# Team13TH.net
KiCad netlist of a schematic drawn in Altium Designer
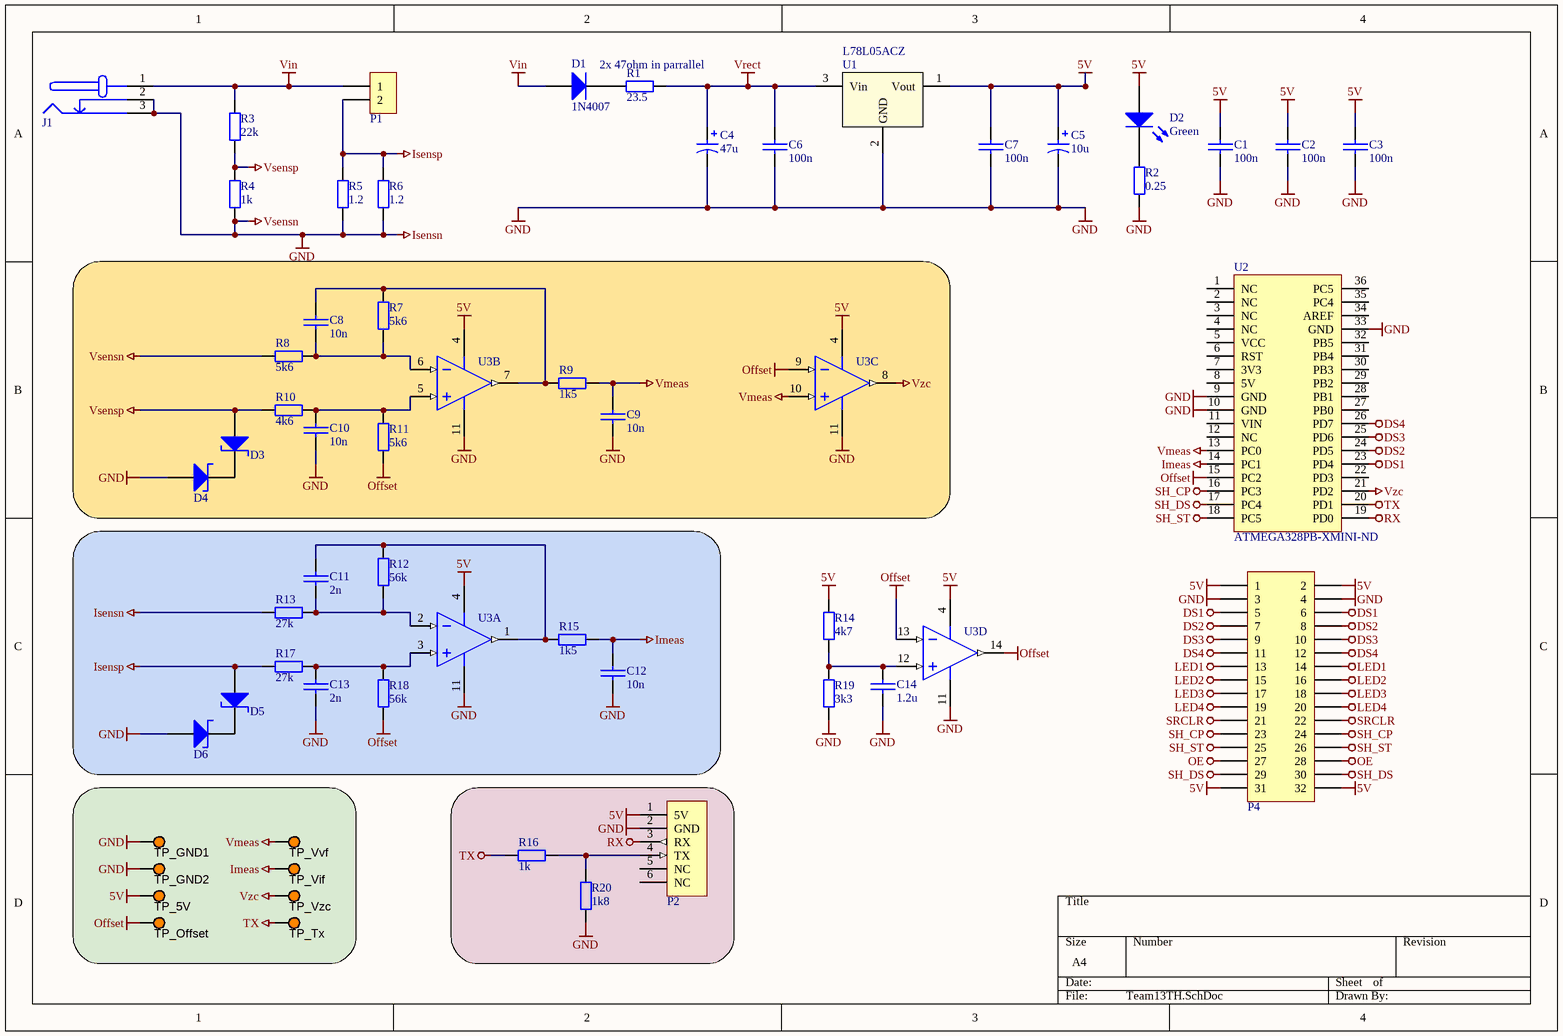
[diagram p0: Team13TH.SchDoc]

(export (version "E")
  (design (tool "Eeschema 10.0.6"))
  (components
    (comp (ref "C1")
      (value "100n")
      (footprint "CCAP-5P0")
      (description "TH ceramic capacitor with 5mm pitch")
      (libsource (lib "EE209_Library") (part "CerCap_TH_5P0"))
    )
    (comp (ref "C2")
      (value "100n")
      (footprint "CCAP-5P0")
      (description "TH ceramic capacitor with 5mm pitch")
      (libsource (lib "EE209_Library") (part "CerCap_TH_5P0"))
    )
    (comp (ref "C3")
      (value "100n")
      (footprint "CCAP-5P0")
      (description "TH ceramic capacitor with 5mm pitch")
      (libsource (lib "EE209_Library") (part "CerCap_TH_5P0"))
    )
    (comp (ref "C4")
      (value "47u")
      (footprint "CAP-RAD-2.5mm Pitch")
      (description "Electrolytic capacitor with radial package, 2mm pitch and 5.2mm diameter")
      (fields (field (name "PUBLISHER") "Altium Limited"))
      (libsource (lib "EE209_Library") (part "ElecCap_TH_2P0"))
    )
    (comp (ref "C5")
      (value "10u")
      (footprint "CAP-RAD-2.5mm Pitch")
      (description "Electrolytic capacitor with radial package, 2mm pitch and 5.2mm diameter")
      (fields (field (name "PUBLISHER") "Altium Limited"))
      (libsource (lib "EE209_Library") (part "ElecCap_TH_2P0"))
    )
    (comp (ref "C6")
      (value "100n")
      (footprint "CCAP-5P0")
      (description "TH ceramic capacitor with 5mm pitch")
      (libsource (lib "EE209_Library") (part "CerCap_TH_5P0"))
    )
    (comp (ref "C7")
      (value "100n")
      (footprint "CCAP-5P0")
      (description "TH ceramic capacitor with 5mm pitch")
      (libsource (lib "EE209_Library") (part "CerCap_TH_5P0"))
    )
    (comp (ref "C8")
      (value "10n")
      (footprint "CCAP-5P0")
      (description "TH ceramic capacitor with 5mm pitch")
      (libsource (lib "EE209_Library") (part "CerCap_TH_5P0"))
    )
    (comp (ref "C9")
      (value "10n")
      (footprint "CCAP-5P0")
      (description "TH ceramic capacitor with 5mm pitch")
      (libsource (lib "EE209_Library") (part "CerCap_TH_5P0"))
    )
    (comp (ref "C10")
      (value "10n")
      (footprint "CCAP-5P0")
      (description "TH ceramic capacitor with 5mm pitch")
      (libsource (lib "EE209_Library") (part "CerCap_TH_5P0"))
    )
    (comp (ref "C11")
      (value "2n")
      (footprint "CCAP-5P0")
      (description "TH ceramic capacitor with 5mm pitch")
      (libsource (lib "EE209_Library") (part "CerCap_TH_5P0"))
    )
    (comp (ref "C12")
      (value "10n")
      (footprint "CCAP-5P0")
      (description "TH ceramic capacitor with 5mm pitch")
      (libsource (lib "EE209_Library") (part "CerCap_TH_5P0"))
    )
    (comp (ref "C13")
      (value "2n")
      (footprint "CCAP-5P0")
      (description "TH ceramic capacitor with 5mm pitch")
      (libsource (lib "EE209_Library") (part "CerCap_TH_5P0"))
    )
    (comp (ref "C14")
      (value "1.2u")
      (footprint "CCAP-5P0")
      (description "TH ceramic capacitor with 5mm pitch")
      (libsource (lib "EE209_Library") (part "CerCap_TH_5P0"))
    )
    (comp (ref "D1")
      (value "1N4007")
      (footprint "1N4007-MFG")
      (description "1N4007 1000V standard axial diode")
      (libsource (lib "EE209_Library") (part "1N4007_TH_4AX0"))
    )
    (comp (ref "D2")
      (value "Green")
      (footprint "LED")
      (description "Typical throughole GaAs LED with 2.54mm pitch")
      (fields (field (name "MANUFACTURER") "Generic Components") (field (name "PUBLISHER") "Altium Limited"))
      (libsource (lib "EE209_Library") (part "LED_TH_2P54"))
    )
    (comp (ref "D3")
      (value "BZX79-CXVX")
      (footprint "AXIAL-Zener-0.4")
      (description "Axial zener diode BZX79 series")
      (fields
        (field (name "MANUFACTURER") "Nexperia USA Inc.")
        (field (name "MANUFACTURER PART NUMBER") "BZX79-C4V7,143")
      )
      (libsource (lib "EE209_Library") (part "Zener_TH_4AX0"))
    )
    (comp (ref "D4")
      (value "BZX79-CXVX")
      (footprint "AXIAL-Zener-0.4")
      (description "Axial zener diode BZX79 series")
      (fields
        (field (name "MANUFACTURER") "Nexperia USA Inc.")
        (field (name "MANUFACTURER PART NUMBER") "BZX79-C4V7,143")
      )
      (libsource (lib "EE209_Library") (part "Zener_TH_4AX0"))
    )
    (comp (ref "D5")
      (value "BZX79-CXVX")
      (footprint "AXIAL-Zener-0.4")
      (description "Axial zener diode BZX79 series")
      (fields
        (field (name "MANUFACTURER") "Nexperia USA Inc.")
        (field (name "MANUFACTURER PART NUMBER") "BZX79-C4V7,143")
      )
      (libsource (lib "EE209_Library") (part "Zener_TH_4AX0"))
    )
    (comp (ref "D6")
      (value "BZX79-CXVX")
      (footprint "AXIAL-Zener-0.4")
      (description "Axial zener diode BZX79 series")
      (fields
        (field (name "MANUFACTURER") "Nexperia USA Inc.")
        (field (name "MANUFACTURER PART NUMBER") "BZX79-C4V7,143")
      )
      (libsource (lib "EE209_Library") (part "Zener_TH_4AX0"))
    )
    (comp (ref "J1")
      (value "DC barrel jack")
      (footprint "AC-Socket")
      (description "DC barrel jack connection to AC source")
      (libsource (lib "EE209_Library") (part "AC_Input"))
    )
    (comp (ref "P1")
      (value "Dual Banana Plugs")
      (footprint "Dual Banana Plug")
      (description "Dual banana plugs connection to the AC load")
      (fields (field (name "PUBLISHER") "Altium Limited"))
      (libsource (lib "EE209_Library") (part "AC_Output"))
    )
    (comp (ref "P2")
      (value "BLE Module Header")
      (footprint "HM10_HDR1X6")
      (description "2.54mm pitch 6-pin header for BLE module")
      (fields (field (name "PUBLISHER") "Altium Limited"))
      (libsource (lib "EE209_Library") (part "BLEModule_TH"))
    )
    (comp (ref "P4")
      (value "Display")
      (footprint "Display")
      (description "16-Pin Header Connecting Display")
      (libsource (lib "EE209_Library") (part "Display"))
    )
    (comp (ref "R1")
      (value "23.5")
      (footprint "AXIAL-0.4")
      (description "Through hole resistor")
      (fields (field (name "PUBLISHER") "Altium Limited"))
      (libsource (lib "") (part "Res_TH_0AX4_1"))
    )
    (comp (ref "R2")
      (value "0.25")
      (footprint "AXIAL-0.4")
      (description "Through hole resistor")
      (fields (field (name "PUBLISHER") "Altium Limited"))
      (libsource (lib "EE209_Library") (part "Res_TH_0AX4"))
    )
    (comp (ref "R3")
      (value "22k")
      (footprint "AXIAL-0.4")
      (description "Through hole resistor")
      (fields (field (name "PUBLISHER") "Altium Limited"))
      (libsource (lib "EE209_Library") (part "Res_TH_0AX4"))
    )
    (comp (ref "R4")
      (value "1k")
      (footprint "AXIAL-0.4")
      (description "Through hole resistor")
      (fields (field (name "PUBLISHER") "Altium Limited"))
      (libsource (lib "EE209_Library") (part "Res_TH_0AX4"))
    )
    (comp (ref "R5")
      (value "1.2")
      (footprint "AXIAL-0.4")
      (description "Through hole resistor")
      (fields (field (name "PUBLISHER") "Altium Limited"))
      (libsource (lib "EE209_Library") (part "Res_TH_0AX4"))
    )
    (comp (ref "R6")
      (value "1.2")
      (footprint "AXIAL-0.4")
      (description "Through hole resistor")
      (fields (field (name "PUBLISHER") "Altium Limited"))
      (libsource (lib "EE209_Library") (part "Res_TH_0AX4"))
    )
    (comp (ref "R7")
      (value "5k6")
      (footprint "AXIAL-0.4")
      (description "Through hole resistor")
      (fields (field (name "PUBLISHER") "Altium Limited"))
      (libsource (lib "EE209_Library") (part "Res_TH_0AX4"))
    )
    (comp (ref "R8")
      (value "5k6")
      (footprint "AXIAL-0.4")
      (description "Through hole resistor")
      (fields (field (name "PUBLISHER") "Altium Limited"))
      (libsource (lib "") (part "Res_TH_0AX4_1"))
    )
    (comp (ref "R9")
      (value "1k5")
      (footprint "AXIAL-0.4")
      (description "Through hole resistor")
      (fields (field (name "PUBLISHER") "Altium Limited"))
      (libsource (lib "") (part "Res_TH_0AX4_1"))
    )
    (comp (ref "R10")
      (value "4k6")
      (footprint "AXIAL-0.4")
      (description "Through hole resistor")
      (fields (field (name "PUBLISHER") "Altium Limited"))
      (libsource (lib "") (part "Res_TH_0AX4_2"))
    )
    (comp (ref "R11")
      (value "5k6")
      (footprint "AXIAL-0.4")
      (description "Through hole resistor")
      (fields (field (name "PUBLISHER") "Altium Limited"))
      (libsource (lib "EE209_Library") (part "Res_TH_0AX4"))
    )
    (comp (ref "R12")
      (value "56k")
      (footprint "AXIAL-0.4")
      (description "Through hole resistor")
      (fields (field (name "PUBLISHER") "Altium Limited"))
      (libsource (lib "EE209_Library") (part "Res_TH_0AX4"))
    )
    (comp (ref "R13")
      (value "27k")
      (footprint "AXIAL-0.4")
      (description "Through hole resistor")
      (fields (field (name "PUBLISHER") "Altium Limited"))
      (libsource (lib "") (part "Res_TH_0AX4_1"))
    )
    (comp (ref "R14")
      (value "4k7")
      (footprint "AXIAL-0.4")
      (description "Through hole resistor")
      (fields (field (name "PUBLISHER") "Altium Limited"))
      (libsource (lib "EE209_Library") (part "Res_TH_0AX4"))
    )
    (comp (ref "R15")
      (value "1k5")
      (footprint "AXIAL-0.4")
      (description "Through hole resistor")
      (fields (field (name "PUBLISHER") "Altium Limited"))
      (libsource (lib "") (part "Res_TH_0AX4_1"))
    )
    (comp (ref "R16")
      (value "1k")
      (footprint "AXIAL-0.4")
      (description "Through hole resistor")
      (fields (field (name "PUBLISHER") "Altium Limited"))
      (libsource (lib "") (part "Res_TH_0AX4_1"))
    )
    (comp (ref "R17")
      (value "27k")
      (footprint "AXIAL-0.4")
      (description "Through hole resistor")
      (fields (field (name "PUBLISHER") "Altium Limited"))
      (libsource (lib "") (part "Res_TH_0AX4_2"))
    )
    (comp (ref "R18")
      (value "56k")
      (footprint "AXIAL-0.4")
      (description "Through hole resistor")
      (fields (field (name "PUBLISHER") "Altium Limited"))
      (libsource (lib "EE209_Library") (part "Res_TH_0AX4"))
    )
    (comp (ref "R19")
      (value "3k3")
      (footprint "AXIAL-0.4")
      (description "Through hole resistor")
      (fields (field (name "PUBLISHER") "Altium Limited"))
      (libsource (lib "EE209_Library") (part "Res_TH_0AX4"))
    )
    (comp (ref "R20")
      (value "1k8")
      (footprint "AXIAL-0.4")
      (description "Through hole resistor")
      (fields (field (name "PUBLISHER") "Altium Limited"))
      (libsource (lib "EE209_Library") (part "Res_TH_0AX4"))
    )
    (comp (ref "TP_5V")
      (value "5003")
      (footprint "TP_TH")
      (description "Test Point, Orange, 1-Pin THD, RoHS")
      (libsource (lib "EE209_Library") (part "TestPoint"))
    )
    (comp (ref "TP_GND1")
      (value "5003")
      (footprint "TP_TH")
      (description "Test Point, Orange, 1-Pin THD, RoHS")
      (libsource (lib "EE209_Library") (part "TestPoint"))
    )
    (comp (ref "TP_GND2")
      (value "5003")
      (footprint "TP_TH")
      (description "Test Point, Orange, 1-Pin THD, RoHS")
      (libsource (lib "EE209_Library") (part "TestPoint"))
    )
    (comp (ref "TP_Offset")
      (value "5003")
      (footprint "TP_TH")
      (description "Test Point, Orange, 1-Pin THD, RoHS")
      (libsource (lib "EE209_Library") (part "TestPoint"))
    )
    (comp (ref "TP_Tx")
      (value "5003")
      (footprint "TP_TH")
      (description "Test Point, Orange, 1-Pin THD, RoHS")
      (libsource (lib "EE209_Library") (part "TestPoint"))
    )
    (comp (ref "TP_Vif")
      (value "5003")
      (footprint "TP_TH")
      (description "Test Point, Orange, 1-Pin THD, RoHS")
      (libsource (lib "EE209_Library") (part "TestPoint"))
    )
    (comp (ref "TP_Vvf")
      (value "5003")
      (footprint "TP_TH")
      (description "Test Point, Orange, 1-Pin THD, RoHS")
      (libsource (lib "EE209_Library") (part "TestPoint"))
    )
    (comp (ref "TP_Vzc")
      (value "5003")
      (footprint "TP_TH")
      (description "Test Point, Orange, 1-Pin THD, RoHS")
      (libsource (lib "EE209_Library") (part "TestPoint"))
    )
    (comp (ref "U1")
      (value "L78L05ACZ")
      (footprint "TO-92")
      (description "Voltage Regulator 5V")
      (fields
        (field (name "MANUFACTURER") "ON Semiconductor")
        (field (name "MANUFACTURER PART NUMBER") "LM78L05ACZX")
      )
      (libsource (lib "EE209_Library") (part "L78L05_TH_TO92"))
    )
    (comp (ref "U2")
      (value "ATmega328PB Xplained Mini Header")
      (footprint "ATmeg328P Xplained")
      (description "Dual 18-pin headers connecting to ATmega328PB Xplained Mini")
      (fields
        (field (name "MANUFACTURER") "Microchip Technology")
        (field (name "MANUFACTURER PART NUMBER") "ATMEGA328PB-XMINI")
        (field (name "SUPPLIER PART NUMBER 1") "ATMEGA328PB-XMINI-ND")
      )
      (libsource (lib "EE209_Library") (part "ATmega328PBXplained_TH"))
    )
    (comp (ref "U3")
      (value "LM324")
      (footprint "DIP-14")
      (description "IC OPAMP GP 14DIP")
      (fields
        (field (name "MANUFACTURER") "ON Semiconductor")
        (field (name "MANUFACTURER PART NUMBER") "LM324N")
      )
      (libsource (lib "EE209_Library") (part "LM324N_TH_DIP16"))
    )
  )
  (nets
    (net (code "1") (name "5V") (class "Default")
      (node (ref "C1") (pin "1") (pinfunction "1_1") (pintype "passive"))
      (node (ref "C2") (pin "1") (pinfunction "1_1") (pintype "passive"))
      (node (ref "C3") (pin "1") (pinfunction "1_1") (pintype "passive"))
      (node (ref "C5") (pin "1") (pinfunction "1_1") (pintype "passive"))
      (node (ref "C7") (pin "1") (pinfunction "1_1") (pintype "passive"))
      (node (ref "D2") (pin "1") (pinfunction "A_1") (pintype "passive"))
      (node (ref "P2") (pin "1") (pinfunction "5V_1") (pintype "passive"))
      (node (ref "P4") (pin "1") (pinfunction "1_1") (pintype "passive"))
      (node (ref "P4") (pin "2") (pinfunction "2_2") (pintype "passive"))
      (node (ref "P4") (pin "31") (pinfunction "31_31") (pintype "passive"))
      (node (ref "P4") (pin "32") (pinfunction "32_32") (pintype "passive"))
      (node (ref "R14") (pin "2") (pinfunction "2_2") (pintype "passive"))
      (node (ref "TP_5V") (pin "1") (pinfunction "1_1") (pintype "passive"))
      (node (ref "U1") (pin "1") (pinfunction "Vout_1") (pintype "passive"))
      (node (ref "U3") (pin "4") (pinfunction "VDD_4") (pintype "power_in"))
    )
    (net (code "2") (name "DS1") (class "Default")
      (node (ref "P4") (pin "5") (pinfunction "5_5") (pintype "passive"))
      (node (ref "P4") (pin "6") (pinfunction "6_6") (pintype "passive"))
      (node (ref "U2") (pin "23") (pinfunction "PD4_23") (pintype "passive"))
    )
    (net (code "3") (name "DS2") (class "Default")
      (node (ref "P4") (pin "7") (pinfunction "7_7") (pintype "passive"))
      (node (ref "P4") (pin "8") (pinfunction "8_8") (pintype "passive"))
      (node (ref "U2") (pin "24") (pinfunction "PD5_24") (pintype "passive"))
    )
    (net (code "4") (name "DS3") (class "Default")
      (node (ref "P4") (pin "10") (pinfunction "10_10") (pintype "passive"))
      (node (ref "P4") (pin "9") (pinfunction "9_9") (pintype "passive"))
      (node (ref "U2") (pin "25") (pinfunction "PD6_25") (pintype "passive"))
    )
    (net (code "5") (name "DS4") (class "Default")
      (node (ref "P4") (pin "11") (pinfunction "11_11") (pintype "passive"))
      (node (ref "P4") (pin "12") (pinfunction "12_12") (pintype "passive"))
      (node (ref "U2") (pin "26") (pinfunction "PD7_26") (pintype "passive"))
    )
    (net (code "6") (name "GND") (class "Default")
      (node (ref "C1") (pin "2") (pinfunction "2_2") (pintype "passive"))
      (node (ref "C10") (pin "2") (pinfunction "2_2") (pintype "passive"))
      (node (ref "C12") (pin "2") (pinfunction "2_2") (pintype "passive"))
      (node (ref "C13") (pin "2") (pinfunction "2_2") (pintype "passive"))
      (node (ref "C14") (pin "2") (pinfunction "2_2") (pintype "passive"))
      (node (ref "C2") (pin "2") (pinfunction "2_2") (pintype "passive"))
      (node (ref "C3") (pin "2") (pinfunction "2_2") (pintype "passive"))
      (node (ref "C4") (pin "2") (pinfunction "2_2") (pintype "passive"))
      (node (ref "C5") (pin "2") (pinfunction "2_2") (pintype "passive"))
      (node (ref "C6") (pin "2") (pinfunction "2_2") (pintype "passive"))
      (node (ref "C7") (pin "2") (pinfunction "2_2") (pintype "passive"))
      (node (ref "C9") (pin "2") (pinfunction "2_2") (pintype "passive"))
      (node (ref "D4") (pin "1") (pinfunction "A_1") (pintype "passive"))
      (node (ref "D6") (pin "1") (pinfunction "A_1") (pintype "passive"))
      (node (ref "J1") (pin "2") (pinfunction "GND_ALT_2") (pintype "power_in"))
      (node (ref "J1") (pin "3") (pinfunction "GND_3") (pintype "power_in"))
      (node (ref "P2") (pin "2") (pinfunction "GND_2") (pintype "passive"))
      (node (ref "P4") (pin "3") (pinfunction "3_3") (pintype "passive"))
      (node (ref "P4") (pin "4") (pinfunction "4_4") (pintype "passive"))
      (node (ref "R13") (pin "1") (pinfunction "1_1") (pintype "passive"))
      (node (ref "R19") (pin "1") (pinfunction "1_1") (pintype "passive"))
      (node (ref "R2") (pin "1") (pinfunction "1_1") (pintype "passive"))
      (node (ref "R20") (pin "1") (pinfunction "1_1") (pintype "passive"))
      (node (ref "R4") (pin "1") (pinfunction "1_1") (pintype "passive"))
      (node (ref "R5") (pin "1") (pinfunction "1_1") (pintype "passive"))
      (node (ref "R6") (pin "1") (pinfunction "1_1") (pintype "passive"))
      (node (ref "R8") (pin "1") (pinfunction "1_1") (pintype "passive"))
      (node (ref "TP_GND1") (pin "1") (pinfunction "1_1") (pintype "passive"))
      (node (ref "TP_GND2") (pin "1") (pinfunction "1_1") (pintype "passive"))
      (node (ref "U1") (pin "2") (pinfunction "GND_2") (pintype "passive"))
      (node (ref "U2") (pin "10") (pinfunction "GND_10") (pintype "power_in"))
      (node (ref "U2") (pin "33") (pinfunction "GND_33") (pintype "passive"))
      (node (ref "U2") (pin "9") (pinfunction "GND_9") (pintype "power_in"))
      (node (ref "U3") (pin "11") (pinfunction "VSS_11") (pintype "power_in"))
    )
    (net (code "7") (name "Imeas") (class "Default")
      (node (ref "C12") (pin "1") (pinfunction "1_1") (pintype "passive"))
      (node (ref "R15") (pin "2") (pinfunction "2_2") (pintype "passive"))
      (node (ref "TP_Vif") (pin "1") (pinfunction "1_1") (pintype "passive"))
      (node (ref "U2") (pin "14") (pinfunction "PC1_14") (pintype "passive"))
    )
    (net (code "8") (name "Isensp") (class "Default")
      (node (ref "D5") (pin "1") (pinfunction "A_1") (pintype "passive"))
      (node (ref "P1") (pin "2") (pinfunction "2_2") (pintype "passive"))
      (node (ref "R17") (pin "2") (pinfunction "2_2") (pintype "passive"))
      (node (ref "R5") (pin "2") (pinfunction "2_2") (pintype "passive"))
      (node (ref "R6") (pin "2") (pinfunction "2_2") (pintype "passive"))
    )
    (net (code "9") (name "LED1") (class "Default")
      (node (ref "P4") (pin "13") (pinfunction "13_13") (pintype "passive"))
      (node (ref "P4") (pin "14") (pinfunction "14_14") (pintype "passive"))
    )
    (net (code "10") (name "LED2") (class "Default")
      (node (ref "P4") (pin "15") (pinfunction "15_15") (pintype "passive"))
      (node (ref "P4") (pin "16") (pinfunction "16_16") (pintype "passive"))
    )
    (net (code "11") (name "LED3") (class "Default")
      (node (ref "P4") (pin "17") (pinfunction "17_17") (pintype "passive"))
      (node (ref "P4") (pin "18") (pinfunction "18_18") (pintype "passive"))
    )
    (net (code "12") (name "LED4") (class "Default")
      (node (ref "P4") (pin "19") (pinfunction "19_19") (pintype "passive"))
      (node (ref "P4") (pin "20") (pinfunction "20_20") (pintype "passive"))
    )
    (net (code "13") (name "Net-(D1-K)") (class "Default")
      (node (ref "D1") (pin "2") (pinfunction "K_2") (pintype "passive"))
      (node (ref "R1") (pin "1") (pinfunction "1_1") (pintype "passive"))
    )
    (net (code "14") (name "Net-(D2-K)") (class "Default")
      (node (ref "D2") (pin "2") (pinfunction "K_2") (pintype "passive"))
      (node (ref "R2") (pin "2") (pinfunction "2_2") (pintype "passive"))
    )
    (net (code "15") (name "Net-(D3-K)") (class "Default")
      (node (ref "D3") (pin "2") (pinfunction "K_2") (pintype "passive"))
      (node (ref "D4") (pin "2") (pinfunction "K_2") (pintype "passive"))
    )
    (net (code "16") (name "Net-(D5-K)") (class "Default")
      (node (ref "D5") (pin "2") (pinfunction "K_2") (pintype "passive"))
      (node (ref "D6") (pin "2") (pinfunction "K_2") (pintype "passive"))
    )
    (net (code "17") (name "Net-(P2-TX)") (class "Default")
      (node (ref "P2") (pin "4") (pinfunction "TX_4") (pintype "input"))
      (node (ref "R16") (pin "2") (pinfunction "2_2") (pintype "passive"))
      (node (ref "R20") (pin "2") (pinfunction "2_2") (pintype "passive"))
    )
    (net (code "18") (name "Net-(U3A-VINA+)") (class "Default")
      (node (ref "C13") (pin "1") (pinfunction "1_1") (pintype "passive"))
      (node (ref "R17") (pin "1") (pinfunction "1_1") (pintype "passive"))
      (node (ref "R18") (pin "2") (pinfunction "2_2") (pintype "passive"))
      (node (ref "U3") (pin "3") (pinfunction "VINA+_3") (pintype "input"))
    )
    (net (code "19") (name "Net-(U3A-VINA-)") (class "Default")
      (node (ref "C11") (pin "2") (pinfunction "2_2") (pintype "passive"))
      (node (ref "R12") (pin "1") (pinfunction "1_1") (pintype "passive"))
      (node (ref "R13") (pin "2") (pinfunction "2_2") (pintype "passive"))
      (node (ref "U3") (pin "2") (pinfunction "VINA-_2") (pintype "input"))
    )
    (net (code "20") (name "Net-(U3A-VOUTA)") (class "Default")
      (node (ref "C11") (pin "1") (pinfunction "1_1") (pintype "passive"))
      (node (ref "R12") (pin "2") (pinfunction "2_2") (pintype "passive"))
      (node (ref "R15") (pin "1") (pinfunction "1_1") (pintype "passive"))
      (node (ref "U3") (pin "1") (pinfunction "VOUTA_1") (pintype "output"))
    )
    (net (code "21") (name "Net-(U3B-VINB+)") (class "Default")
      (node (ref "C10") (pin "1") (pinfunction "1_1") (pintype "passive"))
      (node (ref "R10") (pin "1") (pinfunction "1_1") (pintype "passive"))
      (node (ref "R11") (pin "2") (pinfunction "2_2") (pintype "passive"))
      (node (ref "U3") (pin "5") (pinfunction "VINB+_5") (pintype "input"))
    )
    (net (code "22") (name "Net-(U3B-VINB-)") (class "Default")
      (node (ref "C8") (pin "2") (pinfunction "2_2") (pintype "passive"))
      (node (ref "R7") (pin "1") (pinfunction "1_1") (pintype "passive"))
      (node (ref "R8") (pin "2") (pinfunction "2_2") (pintype "passive"))
      (node (ref "U3") (pin "6") (pinfunction "VINB-_6") (pintype "input"))
    )
    (net (code "23") (name "Net-(U3B-VOUTB)") (class "Default")
      (node (ref "C8") (pin "1") (pinfunction "1_1") (pintype "passive"))
      (node (ref "R7") (pin "2") (pinfunction "2_2") (pintype "passive"))
      (node (ref "R9") (pin "1") (pinfunction "1_1") (pintype "passive"))
      (node (ref "U3") (pin "7") (pinfunction "VOUTB_7") (pintype "output"))
    )
    (net (code "24") (name "Net-(U3D-VIND+)") (class "Default")
      (node (ref "C14") (pin "1") (pinfunction "1_1") (pintype "passive"))
      (node (ref "R14") (pin "1") (pinfunction "1_1") (pintype "passive"))
      (node (ref "R19") (pin "2") (pinfunction "2_2") (pintype "passive"))
      (node (ref "U3") (pin "12") (pinfunction "VIND+_12") (pintype "input"))
    )
    (net (code "25") (name "OE") (class "Default")
      (node (ref "P4") (pin "27") (pinfunction "27_27") (pintype "passive"))
      (node (ref "P4") (pin "28") (pinfunction "28_28") (pintype "passive"))
    )
    (net (code "26") (name "Offset") (class "Default")
      (node (ref "R11") (pin "1") (pinfunction "1_1") (pintype "passive"))
      (node (ref "R18") (pin "1") (pinfunction "1_1") (pintype "passive"))
      (node (ref "TP_Offset") (pin "1") (pinfunction "1_1") (pintype "passive"))
      (node (ref "U2") (pin "15") (pinfunction "PC2_15") (pintype "passive"))
      (node (ref "U3") (pin "13") (pinfunction "VIND-_13") (pintype "input"))
      (node (ref "U3") (pin "14") (pinfunction "VOUTD_14") (pintype "output"))
      (node (ref "U3") (pin "9") (pinfunction "VINC-_9") (pintype "input"))
    )
    (net (code "27") (name "RX") (class "Default")
      (node (ref "P2") (pin "3") (pinfunction "RX_3") (pintype "output"))
      (node (ref "U2") (pin "19") (pinfunction "PD0_19") (pintype "passive"))
    )
    (net (code "28") (name "SH_CP") (class "Default")
      (node (ref "P4") (pin "23") (pinfunction "23_23") (pintype "passive"))
      (node (ref "P4") (pin "24") (pinfunction "24_24") (pintype "passive"))
      (node (ref "U2") (pin "16") (pinfunction "PC3_16") (pintype "passive"))
    )
    (net (code "29") (name "SH_DS") (class "Default")
      (node (ref "P4") (pin "29") (pinfunction "29_29") (pintype "passive"))
      (node (ref "P4") (pin "30") (pinfunction "30_30") (pintype "passive"))
      (node (ref "U2") (pin "17") (pinfunction "PC4_17") (pintype "passive"))
    )
    (net (code "30") (name "SH_ST") (class "Default")
      (node (ref "P4") (pin "25") (pinfunction "25_25") (pintype "passive"))
      (node (ref "P4") (pin "26") (pinfunction "26_26") (pintype "passive"))
      (node (ref "U2") (pin "18") (pinfunction "PC5_18") (pintype "passive"))
    )
    (net (code "31") (name "SRCLR") (class "Default")
      (node (ref "P4") (pin "21") (pinfunction "21_21") (pintype "passive"))
      (node (ref "P4") (pin "22") (pinfunction "22_22") (pintype "passive"))
    )
    (net (code "32") (name "TX") (class "Default")
      (node (ref "R16") (pin "1") (pinfunction "1_1") (pintype "passive"))
      (node (ref "TP_Tx") (pin "1") (pinfunction "1_1") (pintype "passive"))
      (node (ref "U2") (pin "20") (pinfunction "PD1_20") (pintype "passive"))
    )
    (net (code "33") (name "Vin") (class "Default")
      (node (ref "D1") (pin "1") (pinfunction "A_1") (pintype "passive"))
      (node (ref "J1") (pin "1") (pinfunction "VCC_1") (pintype "power_in"))
      (node (ref "P1") (pin "1") (pinfunction "1_1") (pintype "passive"))
      (node (ref "R3") (pin "2") (pinfunction "2_2") (pintype "passive"))
    )
    (net (code "34") (name "Vmeas") (class "Default")
      (node (ref "C9") (pin "1") (pinfunction "1_1") (pintype "passive"))
      (node (ref "R9") (pin "2") (pinfunction "2_2") (pintype "passive"))
      (node (ref "TP_Vvf") (pin "1") (pinfunction "1_1") (pintype "passive"))
      (node (ref "U2") (pin "13") (pinfunction "PC0_13") (pintype "passive"))
      (node (ref "U3") (pin "10") (pinfunction "VINC+_10") (pintype "input"))
    )
    (net (code "35") (name "Vrect") (class "Default")
      (node (ref "C4") (pin "1") (pinfunction "1_1") (pintype "passive"))
      (node (ref "C6") (pin "1") (pinfunction "1_1") (pintype "passive"))
      (node (ref "R1") (pin "2") (pinfunction "2_2") (pintype "passive"))
      (node (ref "U1") (pin "3") (pinfunction "Vin_3") (pintype "passive"))
    )
    (net (code "36") (name "Vsensp") (class "Default")
      (node (ref "D3") (pin "1") (pinfunction "A_1") (pintype "passive"))
      (node (ref "R10") (pin "2") (pinfunction "2_2") (pintype "passive"))
      (node (ref "R3") (pin "1") (pinfunction "1_1") (pintype "passive"))
      (node (ref "R4") (pin "2") (pinfunction "2_2") (pintype "passive"))
    )
    (net (code "37") (name "Vzc") (class "Default")
      (node (ref "TP_Vzc") (pin "1") (pinfunction "1_1") (pintype "passive"))
      (node (ref "U2") (pin "21") (pinfunction "PD2_21") (pintype "passive"))
      (node (ref "U3") (pin "8") (pinfunction "VOUTC_8") (pintype "output"))
    )
    (net (code "38") (name "unconnected-(P2-NC-Pad5)") (class "Default")
      (node (ref "P2") (pin "5") (pinfunction "NC_5") (pintype "passive"))
    )
    (net (code "39") (name "unconnected-(P2-NC-Pad6)") (class "Default")
      (node (ref "P2") (pin "6") (pinfunction "NC_6") (pintype "passive"))
    )
    (net (code "40") (name "unconnected-(U2-3V3-Pad7)") (class "Default")
      (node (ref "U2") (pin "7") (pinfunction "3V3_7") (pintype "passive"))
    )
    (net (code "41") (name "unconnected-(U2-5V-Pad8)") (class "Default")
      (node (ref "U2") (pin "8") (pinfunction "5V_8") (pintype "power_in"))
    )
    (net (code "42") (name "unconnected-(U2-AREF-Pad34)") (class "Default")
      (node (ref "U2") (pin "34") (pinfunction "AREF_34") (pintype "passive"))
    )
    (net (code "43") (name "unconnected-(U2-NC-Pad1)") (class "Default")
      (node (ref "U2") (pin "1") (pinfunction "NC_1") (pintype "passive"))
    )
    (net (code "44") (name "unconnected-(U2-NC-Pad2)") (class "Default")
      (node (ref "U2") (pin "2") (pinfunction "NC_2") (pintype "passive"))
    )
    (net (code "45") (name "unconnected-(U2-NC-Pad3)") (class "Default")
      (node (ref "U2") (pin "3") (pinfunction "NC_3") (pintype "passive"))
    )
    (net (code "46") (name "unconnected-(U2-NC-Pad4)") (class "Default")
      (node (ref "U2") (pin "4") (pinfunction "NC_4") (pintype "passive"))
    )
    (net (code "47") (name "unconnected-(U2-NC-Pad12)") (class "Default")
      (node (ref "U2") (pin "12") (pinfunction "NC_12") (pintype "passive"))
    )
    (net (code "48") (name "unconnected-(U2-PB0-Pad27)") (class "Default")
      (node (ref "U2") (pin "27") (pinfunction "PB0_27") (pintype "passive"))
    )
    (net (code "49") (name "unconnected-(U2-PB1-Pad28)") (class "Default")
      (node (ref "U2") (pin "28") (pinfunction "PB1_28") (pintype "passive"))
    )
    (net (code "50") (name "unconnected-(U2-PB2-Pad29)") (class "Default")
      (node (ref "U2") (pin "29") (pinfunction "PB2_29") (pintype "passive"))
    )
    (net (code "51") (name "unconnected-(U2-PB3-Pad30)") (class "Default")
      (node (ref "U2") (pin "30") (pinfunction "PB3_30") (pintype "passive"))
    )
    (net (code "52") (name "unconnected-(U2-PB4-Pad31)") (class "Default")
      (node (ref "U2") (pin "31") (pinfunction "PB4_31") (pintype "passive"))
    )
    (net (code "53") (name "unconnected-(U2-PB5-Pad32)") (class "Default")
      (node (ref "U2") (pin "32") (pinfunction "PB5_32") (pintype "passive"))
    )
    (net (code "54") (name "unconnected-(U2-PC4-Pad35)") (class "Default")
      (node (ref "U2") (pin "35") (pinfunction "PC4_35") (pintype "passive"))
    )
    (net (code "55") (name "unconnected-(U2-PC5-Pad36)") (class "Default")
      (node (ref "U2") (pin "36") (pinfunction "PC5_36") (pintype "passive"))
    )
    (net (code "56") (name "unconnected-(U2-PD3-Pad22)") (class "Default")
      (node (ref "U2") (pin "22") (pinfunction "PD3_22") (pintype "passive"))
    )
    (net (code "57") (name "unconnected-(U2-RST-Pad6)") (class "Default")
      (node (ref "U2") (pin "6") (pinfunction "RST_6") (pintype "passive"))
    )
    (net (code "58") (name "unconnected-(U2-VCC-Pad5)") (class "Default")
      (node (ref "U2") (pin "5") (pinfunction "VCC_5") (pintype "power_in"))
    )
    (net (code "59") (name "unconnected-(U2-VIN-Pad11)") (class "Default")
      (node (ref "U2") (pin "11") (pinfunction "VIN_11") (pintype "power_in"))
    )
  )
)
